# P_Power.net
KiCad netlist of a schematic drawn in Altium Designer
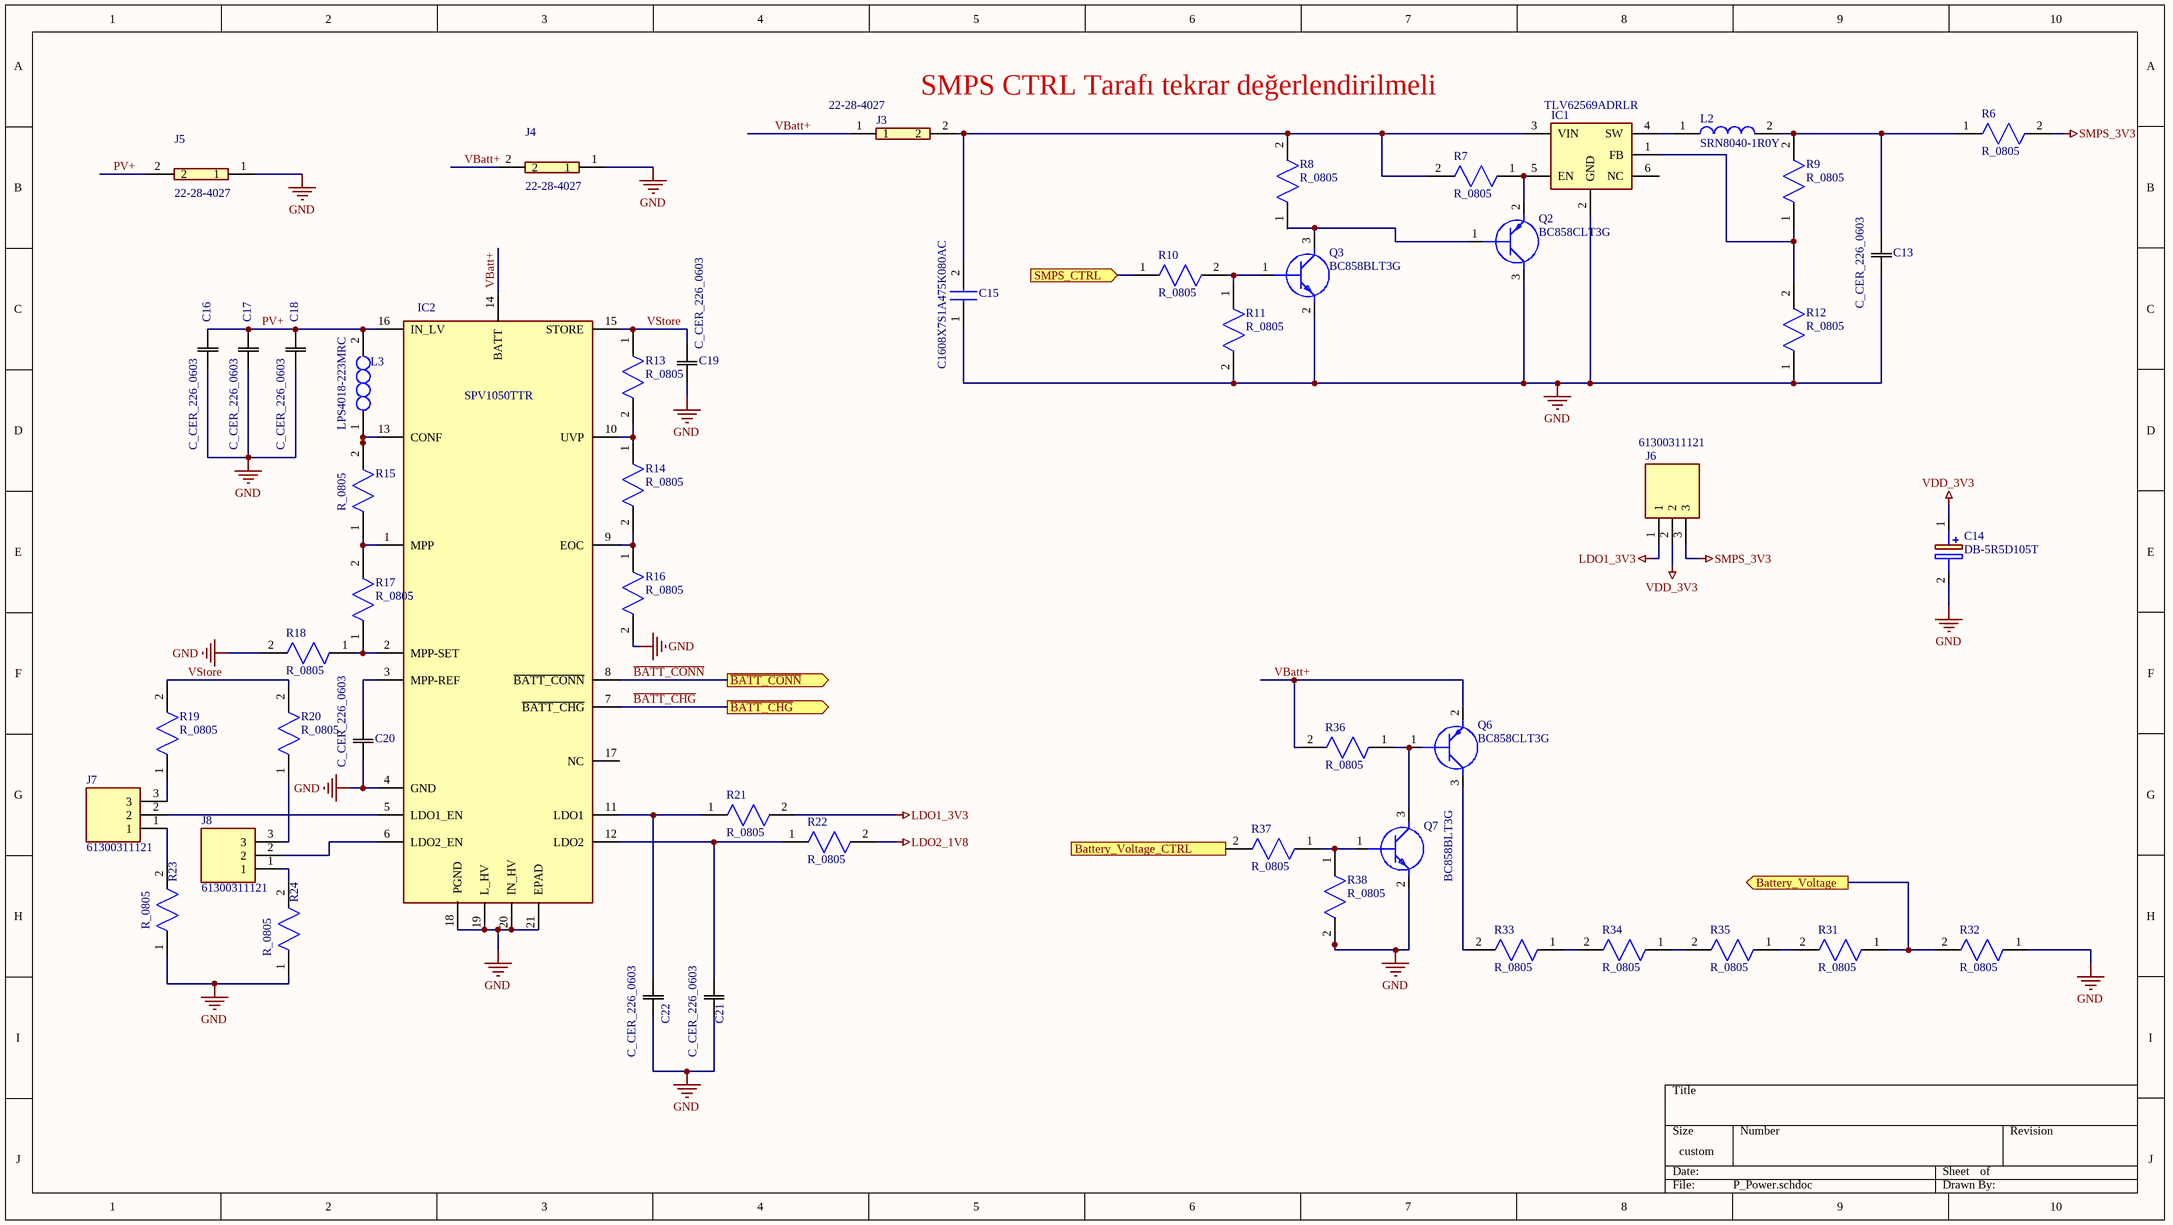
[diagram p0: P_Power.schdoc]

(export (version "E")
  (design (tool "Eeschema 10.0.6"))
  (components
    (comp (ref "C13")
      (value "C_CER_226_0603")
      (footprint "CAPC1608X90N")
      (fields
        (field (name "MANUFACTURER_PART_NUMBER") "GRM188R60J226MEA0D")
        (field (name "COPYRIGHT") "Copyright (C) 2015 Accelerated Designs. All rights reserved")
      )
      (libsource (lib "Main") (part "C_CER_226_0603"))
    )
    (comp (ref "C14")
      (value "DB-5R5D105T")
      (footprint "CAPPRD500W130D2150H800")
      (description "Capacitor Polarised")
      (fields (field (name "MOUSER2 PART NUMBER") "555-DB-5R5D105T"))
      (libsource (lib "Main") (part "DB-5R5D105T"))
    )
    (comp (ref "C15")
      (value "C1608X7S1A475K080AC")
      (footprint "SamacSys:CAPC1608X90N")
      (description "Capacitor")
      (libsource (lib "Main") (part "C1608X7S1A475K080AC"))
    )
    (comp (ref "C16")
      (value "C_CER_226_0603")
      (footprint "CAPC1608X90N")
      (fields
        (field (name "MANUFACTURER_PART_NUMBER") "GRM188R60J226MEA0D")
        (field (name "COPYRIGHT") "Copyright (C) 2015 Accelerated Designs. All rights reserved")
      )
      (libsource (lib "Main") (part "C_CER_226_0603"))
    )
    (comp (ref "C17")
      (value "C_CER_226_0603")
      (footprint "CAPC1608X90N")
      (fields
        (field (name "MANUFACTURER_PART_NUMBER") "GRM188R60J226MEA0D")
        (field (name "COPYRIGHT") "Copyright (C) 2015 Accelerated Designs. All rights reserved")
      )
      (libsource (lib "Main") (part "C_CER_226_0603"))
    )
    (comp (ref "C18")
      (value "C_CER_226_0603")
      (footprint "CAPC1608X90N")
      (fields
        (field (name "MANUFACTURER_PART_NUMBER") "GRM188R60J226MEA0D")
        (field (name "COPYRIGHT") "Copyright (C) 2015 Accelerated Designs. All rights reserved")
      )
      (libsource (lib "Main") (part "C_CER_226_0603"))
    )
    (comp (ref "C19")
      (value "C_CER_226_0603")
      (footprint "CAPC1608X90N")
      (fields
        (field (name "MANUFACTURER_PART_NUMBER") "GRM188R60J226MEA0D")
        (field (name "COPYRIGHT") "Copyright (C) 2015 Accelerated Designs. All rights reserved")
      )
      (libsource (lib "Main") (part "C_CER_226_0603"))
    )
    (comp (ref "C20")
      (value "C_CER_226_0603")
      (footprint "CAPC1608X90N")
      (fields
        (field (name "MANUFACTURER_PART_NUMBER") "GRM188R60J226MEA0D")
        (field (name "COPYRIGHT") "Copyright (C) 2015 Accelerated Designs. All rights reserved")
      )
      (libsource (lib "Main") (part "C_CER_226_0603"))
    )
    (comp (ref "C21")
      (value "C_CER_226_0603")
      (footprint "CAPC1608X90N")
      (fields
        (field (name "MANUFACTURER_PART_NUMBER") "GRM188R60J226MEA0D")
        (field (name "COPYRIGHT") "Copyright (C) 2015 Accelerated Designs. All rights reserved")
      )
      (libsource (lib "Main") (part "C_CER_226_0603"))
    )
    (comp (ref "C22")
      (value "C_CER_226_0603")
      (footprint "CAPC1608X90N")
      (fields
        (field (name "MANUFACTURER_PART_NUMBER") "GRM188R60J226MEA0D")
        (field (name "COPYRIGHT") "Copyright (C) 2015 Accelerated Designs. All rights reserved")
      )
      (libsource (lib "Main") (part "C_CER_226_0603"))
    )
    (comp (ref "IC1")
      (value "TLV62569ADRLR")
      (footprint "SOTFL50P160X60-6N")
      (description "Integrated Circuit")
      (libsource (lib "Main") (part "TLV62569ADRLR"))
    )
    (comp (ref "IC2")
      (value "SPV1050TTR")
      (footprint "QFN40P300X300X100-21N-D")
      (description "Integrated Circuit")
      (fields (field (name "MOUSER2 PART NUMBER") "511-SPV1050TTR"))
      (libsource (lib "Main") (part "SPV1050TTR"))
    )
    (comp (ref "J3")
      (value "22-28-4027")
      (footprint "HDRV2W66P0X254_1X2_508X249X1067P")
      (description "Connector")
      (fields (field (name "MOUSER2 PART NUMBER") "538-22-28-4027"))
      (libsource (lib "Main") (part "22-28-4027"))
    )
    (comp (ref "J4")
      (value "22-28-4027")
      (footprint "HDRV2W66P0X254_1X2_508X249X1067P")
      (description "Connector")
      (fields (field (name "MOUSER2 PART NUMBER") "538-22-28-4027"))
      (libsource (lib "") (part "22-28-4027_1"))
    )
    (comp (ref "J5")
      (value "22-28-4027")
      (footprint "HDRV2W66P0X254_1X2_508X249X1067P")
      (description "Connector")
      (fields (field (name "MOUSER2 PART NUMBER") "538-22-28-4027"))
      (libsource (lib "") (part "22-28-4027_1"))
    )
    (comp (ref "J6")
      (value "61300311121")
      (footprint "SamacSys:HDRV3W95P0X254_1X3_762X254X869P")
      (description "Connector")
      (fields (field (name "MOUSER2 PART NUMBER") "710-61300311121"))
      (libsource (lib "") (part "61300311121_1"))
    )
    (comp (ref "J7")
      (value "61300311121")
      (footprint "SamacSys:HDRV3W95P0X254_1X3_762X254X869P")
      (description "Connector")
      (fields (field (name "MOUSER2 PART NUMBER") "710-61300311121"))
      (libsource (lib "Main") (part "61300311121"))
    )
    (comp (ref "J8")
      (value "61300311121")
      (footprint "SamacSys:HDRV3W95P0X254_1X3_762X254X869P")
      (description "Connector")
      (fields (field (name "MOUSER2 PART NUMBER") "710-61300311121"))
      (libsource (lib "Main") (part "61300311121"))
    )
    (comp (ref "L2")
      (value "SRN8040-1R0Y")
      (footprint "SRN80408R2Y")
      (description "Inductor")
      (libsource (lib "Main") (part "SRN8040-1R0Y"))
    )
    (comp (ref "L3")
      (value "LPS4018-223MRC")
      (footprint "SamacSys:LPS4018223MRC")
      (description "Inductor")
      (fields (field (name "MOUSER2 PART NUMBER") "994-LPS4018-223MRC"))
      (libsource (lib "Main") (part "LPS4018-223MRC"))
    )
    (comp (ref "Q2")
      (value "BC858CLT3G")
      (footprint "BC858CLT3G")
      (description "Transistor BJT PNP")
      (fields (field (name "MOUSER2 PART NUMBER") "863-BC858CLT3G"))
      (libsource (lib "SamacSys") (part "BC858CLT3G"))
    )
    (comp (ref "Q3")
      (value "BC858BLT3G")
      (footprint "SOT96P237X111-3N")
      (description "Transistor BJT PNP")
      (libsource (lib "SamacSys") (part "BC858BLT3G"))
    )
    (comp (ref "Q6")
      (value "BC858CLT3G")
      (footprint "BC858CLT3G")
      (description "Transistor BJT PNP")
      (fields (field (name "MOUSER2 PART NUMBER") "863-BC858CLT3G"))
      (libsource (lib "SamacSys") (part "BC858CLT3G"))
    )
    (comp (ref "Q7")
      (value "BC858BLT3G")
      (footprint "SOT96P237X111-3N")
      (description "Transistor BJT PNP")
      (libsource (lib "SamacSys") (part "BC858BLT3G"))
    )
    (comp (ref "R6")
      (value "R_0805")
      (footprint "RESC2012X55N")
      (description "Resistor")
      (libsource (lib "Main") (part "R_0805"))
    )
    (comp (ref "R7")
      (value "R_0805")
      (footprint "RESC2012X55N")
      (description "Resistor")
      (libsource (lib "Main") (part "R_0805"))
    )
    (comp (ref "R8")
      (value "R_0805")
      (footprint "RESC2012X55N")
      (description "Resistor")
      (libsource (lib "Main") (part "R_0805"))
    )
    (comp (ref "R9")
      (value "R_0805")
      (footprint "RESC2012X55N")
      (description "Resistor")
      (libsource (lib "Main") (part "R_0805"))
    )
    (comp (ref "R10")
      (value "R_0805")
      (footprint "RESC2012X55N")
      (description "Resistor")
      (libsource (lib "Main") (part "R_0805"))
    )
    (comp (ref "R11")
      (value "R_0805")
      (footprint "RESC2012X55N")
      (description "Resistor")
      (libsource (lib "Main") (part "R_0805"))
    )
    (comp (ref "R12")
      (value "R_0805")
      (footprint "RESC2012X55N")
      (description "Resistor")
      (libsource (lib "Main") (part "R_0805"))
    )
    (comp (ref "R13")
      (value "R_0805")
      (footprint "RESC2012X55N")
      (description "Resistor")
      (libsource (lib "Main") (part "R_0805"))
    )
    (comp (ref "R14")
      (value "R_0805")
      (footprint "RESC2012X55N")
      (description "Resistor")
      (libsource (lib "Main") (part "R_0805"))
    )
    (comp (ref "R15")
      (value "R_0805")
      (footprint "RESC2012X55N")
      (description "Resistor")
      (libsource (lib "Main") (part "R_0805"))
    )
    (comp (ref "R16")
      (value "R_0805")
      (footprint "RESC2012X55N")
      (description "Resistor")
      (libsource (lib "Main") (part "R_0805"))
    )
    (comp (ref "R17")
      (value "R_0805")
      (footprint "RESC2012X55N")
      (description "Resistor")
      (libsource (lib "Main") (part "R_0805"))
    )
    (comp (ref "R18")
      (value "R_0805")
      (footprint "RESC2012X55N")
      (description "Resistor")
      (libsource (lib "Main") (part "R_0805"))
    )
    (comp (ref "R19")
      (value "R_0805")
      (footprint "RESC2012X55N")
      (description "Resistor")
      (libsource (lib "Main") (part "R_0805"))
    )
    (comp (ref "R20")
      (value "R_0805")
      (footprint "RESC2012X55N")
      (description "Resistor")
      (libsource (lib "Main") (part "R_0805"))
    )
    (comp (ref "R21")
      (value "R_0805")
      (footprint "RESC2012X55N")
      (description "Resistor")
      (libsource (lib "Main") (part "R_0805"))
    )
    (comp (ref "R22")
      (value "R_0805")
      (footprint "RESC2012X55N")
      (description "Resistor")
      (libsource (lib "Main") (part "R_0805"))
    )
    (comp (ref "R23")
      (value "R_0805")
      (footprint "RESC2012X55N")
      (description "Resistor")
      (libsource (lib "Main") (part "R_0805"))
    )
    (comp (ref "R24")
      (value "R_0805")
      (footprint "RESC2012X55N")
      (description "Resistor")
      (libsource (lib "Main") (part "R_0805"))
    )
    (comp (ref "R31")
      (value "R_0805")
      (footprint "RESC2012X55N")
      (description "Resistor")
      (libsource (lib "Main") (part "R_0805"))
    )
    (comp (ref "R32")
      (value "R_0805")
      (footprint "RESC2012X55N")
      (description "Resistor")
      (libsource (lib "Main") (part "R_0805"))
    )
    (comp (ref "R33")
      (value "R_0805")
      (footprint "RESC2012X55N")
      (description "Resistor")
      (libsource (lib "Main") (part "R_0805"))
    )
    (comp (ref "R34")
      (value "R_0805")
      (footprint "RESC2012X55N")
      (description "Resistor")
      (libsource (lib "Main") (part "R_0805"))
    )
    (comp (ref "R35")
      (value "R_0805")
      (footprint "RESC2012X55N")
      (description "Resistor")
      (libsource (lib "Main") (part "R_0805"))
    )
    (comp (ref "R36")
      (value "R_0805")
      (footprint "RESC2012X55N")
      (description "Resistor")
      (libsource (lib "Main") (part "R_0805"))
    )
    (comp (ref "R37")
      (value "R_0805")
      (footprint "RESC2012X55N")
      (description "Resistor")
      (libsource (lib "Main") (part "R_0805"))
    )
    (comp (ref "R38")
      (value "R_0805")
      (footprint "RESC2012X55N")
      (description "Resistor")
      (libsource (lib "Main") (part "R_0805"))
    )
  )
  (nets
    (net (code "1") (name "/Battery_Voltage") (class "Default")
      (node (ref "R31") (pin "1") (pinfunction "1_1") (pintype "passive"))
      (node (ref "R32") (pin "2") (pinfunction "2_2") (pintype "passive"))
    )
    (net (code "2") (name "/Battery_Voltage_CTRL") (class "Default")
      (node (ref "R37") (pin "2") (pinfunction "2_2") (pintype "passive"))
    )
    (net (code "3") (name "/PV+") (class "Default")
      (node (ref "C16") (pin "2") (pinfunction "2_2") (pintype "passive"))
      (node (ref "C17") (pin "2") (pinfunction "2_2") (pintype "passive"))
      (node (ref "C18") (pin "2") (pinfunction "2_2") (pintype "passive"))
      (node (ref "IC2") (pin "16") (pinfunction "IN_LV_16") (pintype "passive"))
      (node (ref "J5") (pin "2") (pinfunction "2_2") (pintype "passive"))
      (node (ref "L3") (pin "2") (pinfunction "2_2") (pintype "passive"))
    )
    (net (code "4") (name "/SMPS_CTRL") (class "Default")
      (node (ref "R10") (pin "1") (pinfunction "1_1") (pintype "passive"))
    )
    (net (code "5") (name "/VBatt+") (class "Default")
      (node (ref "IC2") (pin "14") (pinfunction "BATT_14") (pintype "passive"))
      (node (ref "J3") (pin "1") (pinfunction "1_1") (pintype "passive"))
      (node (ref "J4") (pin "2") (pinfunction "2_2") (pintype "passive"))
      (node (ref "Q6") (pin "2") (pinfunction "E_2") (pintype "passive"))
      (node (ref "R36") (pin "2") (pinfunction "2_2") (pintype "passive"))
    )
    (net (code "6") (name "/VStore") (class "Default")
      (node (ref "C19") (pin "2") (pinfunction "2_2") (pintype "passive"))
      (node (ref "IC2") (pin "15") (pinfunction "STORE_15") (pintype "passive"))
      (node (ref "R13") (pin "1") (pinfunction "1_1") (pintype "passive"))
      (node (ref "R19") (pin "2") (pinfunction "2_2") (pintype "passive"))
      (node (ref "R20") (pin "2") (pinfunction "2_2") (pintype "passive"))
    )
    (net (code "7") (name "/~{BATT_CHG}") (class "Default")
      (node (ref "IC2") (pin "7") (pinfunction "~{BATT_CHG}_7") (pintype "passive"))
    )
    (net (code "8") (name "/~{BATT_CONN}") (class "Default")
      (node (ref "IC2") (pin "8") (pinfunction "~{BATT_CONN}_8") (pintype "passive"))
    )
    (net (code "9") (name "GND") (class "Default")
      (node (ref "C13") (pin "1") (pinfunction "1_1") (pintype "passive"))
      (node (ref "C14") (pin "2") (pinfunction "-_2") (pintype "passive"))
      (node (ref "C15") (pin "1") (pinfunction "1_1") (pintype "passive"))
      (node (ref "C16") (pin "1") (pinfunction "1_1") (pintype "passive"))
      (node (ref "C17") (pin "1") (pinfunction "1_1") (pintype "passive"))
      (node (ref "C18") (pin "1") (pinfunction "1_1") (pintype "passive"))
      (node (ref "C19") (pin "1") (pinfunction "1_1") (pintype "passive"))
      (node (ref "C20") (pin "1") (pinfunction "1_1") (pintype "passive"))
      (node (ref "C21") (pin "1") (pinfunction "1_1") (pintype "passive"))
      (node (ref "C22") (pin "1") (pinfunction "1_1") (pintype "passive"))
      (node (ref "IC1") (pin "2") (pinfunction "GND_2") (pintype "passive"))
      (node (ref "IC2") (pin "18") (pinfunction "PGND_18") (pintype "passive"))
      (node (ref "IC2") (pin "19") (pinfunction "L_HV_19") (pintype "passive"))
      (node (ref "IC2") (pin "20") (pinfunction "IN_HV_20") (pintype "passive"))
      (node (ref "IC2") (pin "21") (pinfunction "EPAD_21") (pintype "passive"))
      (node (ref "IC2") (pin "4") (pinfunction "GND_4") (pintype "passive"))
      (node (ref "J4") (pin "1") (pinfunction "1_1") (pintype "passive"))
      (node (ref "J5") (pin "1") (pinfunction "1_1") (pintype "passive"))
      (node (ref "Q2") (pin "3") (pinfunction "C_3") (pintype "passive"))
      (node (ref "Q3") (pin "2") (pinfunction "E_2") (pintype "passive"))
      (node (ref "Q7") (pin "2") (pinfunction "E_2") (pintype "passive"))
      (node (ref "R11") (pin "2") (pinfunction "2_2") (pintype "passive"))
      (node (ref "R12") (pin "1") (pinfunction "1_1") (pintype "passive"))
      (node (ref "R16") (pin "2") (pinfunction "2_2") (pintype "passive"))
      (node (ref "R18") (pin "2") (pinfunction "2_2") (pintype "passive"))
      (node (ref "R23") (pin "1") (pinfunction "1_1") (pintype "passive"))
      (node (ref "R24") (pin "1") (pinfunction "1_1") (pintype "passive"))
      (node (ref "R32") (pin "1") (pinfunction "1_1") (pintype "passive"))
      (node (ref "R38") (pin "2") (pinfunction "2_2") (pintype "passive"))
    )
    (net (code "10") (name "LDO1_3V3") (class "Default")
      (node (ref "J6") (pin "1") (pinfunction "1_1") (pintype "passive"))
      (node (ref "R21") (pin "2") (pinfunction "2_2") (pintype "passive"))
    )
    (net (code "11") (name "LDO2_1V8") (class "Default")
      (node (ref "R22") (pin "2") (pinfunction "2_2") (pintype "passive"))
    )
    (net (code "12") (name "Net-(C13-Pad2)") (class "Default")
      (node (ref "C13") (pin "2") (pinfunction "2_2") (pintype "passive"))
      (node (ref "L2") (pin "2") (pinfunction "2_2") (pintype "passive"))
      (node (ref "R6") (pin "1") (pinfunction "1_1") (pintype "passive"))
      (node (ref "R9") (pin "2") (pinfunction "2_2") (pintype "passive"))
    )
    (net (code "13") (name "Net-(IC1-EN)") (class "Default")
      (node (ref "IC1") (pin "5") (pinfunction "EN_5") (pintype "passive"))
      (node (ref "Q2") (pin "2") (pinfunction "E_2") (pintype "passive"))
      (node (ref "R7") (pin "1") (pinfunction "1_1") (pintype "passive"))
    )
    (net (code "14") (name "Net-(IC1-FB)") (class "Default")
      (node (ref "IC1") (pin "1") (pinfunction "FB_1") (pintype "passive"))
      (node (ref "R12") (pin "2") (pinfunction "2_2") (pintype "passive"))
      (node (ref "R9") (pin "1") (pinfunction "1_1") (pintype "passive"))
    )
    (net (code "15") (name "Net-(IC1-SW)") (class "Default")
      (node (ref "IC1") (pin "4") (pinfunction "SW_4") (pintype "passive"))
      (node (ref "L2") (pin "1") (pinfunction "1_1") (pintype "passive"))
    )
    (net (code "16") (name "Net-(IC1-VIN)") (class "Default")
      (node (ref "C15") (pin "2") (pinfunction "2_2") (pintype "passive"))
      (node (ref "IC1") (pin "3") (pinfunction "VIN_3") (pintype "passive"))
      (node (ref "J3") (pin "2") (pinfunction "2_2") (pintype "passive"))
      (node (ref "R7") (pin "2") (pinfunction "2_2") (pintype "passive"))
      (node (ref "R8") (pin "2") (pinfunction "2_2") (pintype "passive"))
    )
    (net (code "17") (name "Net-(IC2-CONF)") (class "Default")
      (node (ref "IC2") (pin "13") (pinfunction "CONF_13") (pintype "passive"))
      (node (ref "L3") (pin "1") (pinfunction "1_1") (pintype "passive"))
      (node (ref "R15") (pin "2") (pinfunction "2_2") (pintype "passive"))
    )
    (net (code "18") (name "Net-(IC2-EOC)") (class "Default")
      (node (ref "IC2") (pin "9") (pinfunction "EOC_9") (pintype "passive"))
      (node (ref "R14") (pin "2") (pinfunction "2_2") (pintype "passive"))
      (node (ref "R16") (pin "1") (pinfunction "1_1") (pintype "passive"))
    )
    (net (code "19") (name "Net-(IC2-LDO1)") (class "Default")
      (node (ref "C22") (pin "2") (pinfunction "2_2") (pintype "passive"))
      (node (ref "IC2") (pin "11") (pinfunction "LDO1_11") (pintype "passive"))
      (node (ref "R21") (pin "1") (pinfunction "1_1") (pintype "passive"))
    )
    (net (code "20") (name "Net-(IC2-LDO1_EN)") (class "Default")
      (node (ref "IC2") (pin "5") (pinfunction "LDO1_EN_5") (pintype "passive"))
      (node (ref "J7") (pin "2") (pinfunction "2_2") (pintype "passive"))
    )
    (net (code "21") (name "Net-(IC2-LDO2)") (class "Default")
      (node (ref "C21") (pin "2") (pinfunction "2_2") (pintype "passive"))
      (node (ref "IC2") (pin "12") (pinfunction "LDO2_12") (pintype "passive"))
      (node (ref "R22") (pin "1") (pinfunction "1_1") (pintype "passive"))
    )
    (net (code "22") (name "Net-(IC2-LDO2_EN)") (class "Default")
      (node (ref "IC2") (pin "6") (pinfunction "LDO2_EN_6") (pintype "passive"))
      (node (ref "J8") (pin "2") (pinfunction "2_2") (pintype "passive"))
    )
    (net (code "23") (name "Net-(IC2-MPP)") (class "Default")
      (node (ref "IC2") (pin "1") (pinfunction "MPP_1") (pintype "passive"))
      (node (ref "R15") (pin "1") (pinfunction "1_1") (pintype "passive"))
      (node (ref "R17") (pin "2") (pinfunction "2_2") (pintype "passive"))
    )
    (net (code "24") (name "Net-(IC2-MPP-REF)") (class "Default")
      (node (ref "C20") (pin "2") (pinfunction "2_2") (pintype "passive"))
      (node (ref "IC2") (pin "3") (pinfunction "MPP-REF_3") (pintype "passive"))
    )
    (net (code "25") (name "Net-(IC2-MPP-SET)") (class "Default")
      (node (ref "IC2") (pin "2") (pinfunction "MPP-SET_2") (pintype "passive"))
      (node (ref "R17") (pin "1") (pinfunction "1_1") (pintype "passive"))
      (node (ref "R18") (pin "1") (pinfunction "1_1") (pintype "passive"))
    )
    (net (code "26") (name "Net-(IC2-UVP)") (class "Default")
      (node (ref "IC2") (pin "10") (pinfunction "UVP_10") (pintype "passive"))
      (node (ref "R13") (pin "2") (pinfunction "2_2") (pintype "passive"))
      (node (ref "R14") (pin "1") (pinfunction "1_1") (pintype "passive"))
    )
    (net (code "27") (name "Net-(J7-Pad1)") (class "Default")
      (node (ref "J7") (pin "1") (pinfunction "1_1") (pintype "passive"))
      (node (ref "R23") (pin "2") (pinfunction "2_2") (pintype "passive"))
    )
    (net (code "28") (name "Net-(J7-Pad3)") (class "Default")
      (node (ref "J7") (pin "3") (pinfunction "3_3") (pintype "passive"))
      (node (ref "R19") (pin "1") (pinfunction "1_1") (pintype "passive"))
    )
    (net (code "29") (name "Net-(J8-Pad1)") (class "Default")
      (node (ref "J8") (pin "1") (pinfunction "1_1") (pintype "passive"))
      (node (ref "R24") (pin "2") (pinfunction "2_2") (pintype "passive"))
    )
    (net (code "30") (name "Net-(J8-Pad3)") (class "Default")
      (node (ref "J8") (pin "3") (pinfunction "3_3") (pintype "passive"))
      (node (ref "R20") (pin "1") (pinfunction "1_1") (pintype "passive"))
    )
    (net (code "31") (name "Net-(Q2-B)") (class "Default")
      (node (ref "Q2") (pin "1") (pinfunction "B_1") (pintype "passive"))
      (node (ref "Q3") (pin "3") (pinfunction "C_3") (pintype "passive"))
      (node (ref "R8") (pin "1") (pinfunction "1_1") (pintype "passive"))
    )
    (net (code "32") (name "Net-(Q3-B)") (class "Default")
      (node (ref "Q3") (pin "1") (pinfunction "B_1") (pintype "passive"))
      (node (ref "R10") (pin "2") (pinfunction "2_2") (pintype "passive"))
      (node (ref "R11") (pin "1") (pinfunction "1_1") (pintype "passive"))
    )
    (net (code "33") (name "Net-(Q6-B)") (class "Default")
      (node (ref "Q6") (pin "1") (pinfunction "B_1") (pintype "passive"))
      (node (ref "Q7") (pin "3") (pinfunction "C_3") (pintype "passive"))
      (node (ref "R36") (pin "1") (pinfunction "1_1") (pintype "passive"))
    )
    (net (code "34") (name "Net-(Q6-C)") (class "Default")
      (node (ref "Q6") (pin "3") (pinfunction "C_3") (pintype "passive"))
      (node (ref "R33") (pin "2") (pinfunction "2_2") (pintype "passive"))
    )
    (net (code "35") (name "Net-(Q7-B)") (class "Default")
      (node (ref "Q7") (pin "1") (pinfunction "B_1") (pintype "passive"))
      (node (ref "R37") (pin "1") (pinfunction "1_1") (pintype "passive"))
      (node (ref "R38") (pin "1") (pinfunction "1_1") (pintype "passive"))
    )
    (net (code "36") (name "Net-(R31-Pad2)") (class "Default")
      (node (ref "R31") (pin "2") (pinfunction "2_2") (pintype "passive"))
      (node (ref "R35") (pin "1") (pinfunction "1_1") (pintype "passive"))
    )
    (net (code "37") (name "Net-(R33-Pad1)") (class "Default")
      (node (ref "R33") (pin "1") (pinfunction "1_1") (pintype "passive"))
      (node (ref "R34") (pin "2") (pinfunction "2_2") (pintype "passive"))
    )
    (net (code "38") (name "Net-(R34-Pad1)") (class "Default")
      (node (ref "R34") (pin "1") (pinfunction "1_1") (pintype "passive"))
      (node (ref "R35") (pin "2") (pinfunction "2_2") (pintype "passive"))
    )
    (net (code "39") (name "SMPS_3V3") (class "Default")
      (node (ref "J6") (pin "3") (pinfunction "3_3") (pintype "passive"))
      (node (ref "R6") (pin "2") (pinfunction "2_2") (pintype "passive"))
    )
    (net (code "40") (name "VDD_3V3") (class "Default")
      (node (ref "C14") (pin "1") (pinfunction "+_1") (pintype "passive"))
      (node (ref "J6") (pin "2") (pinfunction "2_2") (pintype "passive"))
    )
    (net (code "41") (name "unconnected-(IC1-NC-Pad6)") (class "Default")
      (node (ref "IC1") (pin "6") (pinfunction "NC_6") (pintype "passive"))
    )
    (net (code "42") (name "unconnected-(IC2-NC-Pad17)") (class "Default")
      (node (ref "IC2") (pin "17") (pinfunction "NC_17") (pintype "passive"))
    )
  )
)
